# Mech_Interface_Port.net
KiCad netlist of a schematic drawn in Altium Designer
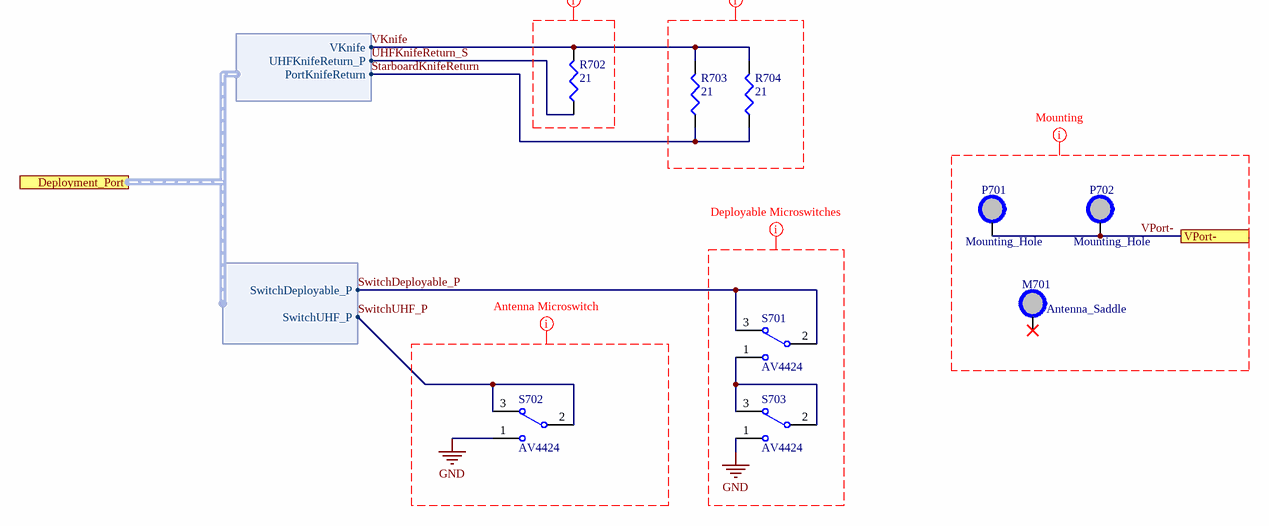
[diagram p0: Mech_Interface_Port.SchDoc]

(export (version "E")
  (design (tool "Eeschema 10.0.6"))
  (components
    (comp (ref "M701")
      (value "Antenna_Saddle")
      (footprint "ANTENNA_SADDLE")
      (fields
        (field (name "PART NUMBER") "PXX-ABS-00001")
        (field (name "MANUFACTURER PART NUMBER") "Custom")
        (field (name "PUBLISHER") "AlbertaSat")
      )
      (libsource (lib "Database") (part "Mounting_Hole"))
    )
    (comp (ref "P701")
      (value "Mounting_Hole")
      (footprint "DEPHINGE_MOUNTING_HOLE_BODY")
      (fields
        (field (name "PART NUMBER") "PXX-ABS-00004")
        (field (name "MANUFACTURER PART NUMBER") "Custom")
        (field (name "PUBLISHER") "AlbertaSat")
      )
      (libsource (lib "Database") (part "Mounting_Hole"))
    )
    (comp (ref "P702")
      (value "Mounting_Hole")
      (footprint "DEPHINGE_MOUNTING_HOLE_BODY")
      (fields
        (field (name "PART NUMBER") "PXX-ABS-00004")
        (field (name "MANUFACTURER PART NUMBER") "Custom")
        (field (name "PUBLISHER") "AlbertaSat")
      )
      (libsource (lib "Database") (part "Mounting_Hole"))
    )
    (comp (ref "R702")
      (value "21")
      (footprint "VSH-CPF1")
      (description "21 Ohms ±1% 1W Through Hole Resistor Axial Flame Proof, Moisture Resistant, Safety Metal Film")
      (fields
        (field (name "PART NUMBER") "PR-VSH-00317")
        (field (name "MANUFACTURER PART NUMBER") "CPF121R000FKEE6")
        (field (name "PUBLISHER") "AlbertaSat")
      )
      (libsource (lib "Database") (part "Res3"))
    )
    (comp (ref "R703")
      (value "21")
      (footprint "VSH-CPF1")
      (description "21 Ohms ±1% 1W Through Hole Resistor Axial Flame Proof, Moisture Resistant, Safety Metal Film")
      (fields
        (field (name "PART NUMBER") "PR-VSH-00317")
        (field (name "MANUFACTURER PART NUMBER") "CPF121R000FKEE6")
        (field (name "PUBLISHER") "AlbertaSat")
      )
      (libsource (lib "Database") (part "Res3"))
    )
    (comp (ref "R704")
      (value "21")
      (footprint "VSH-CPF1")
      (description "21 Ohms ±1% 1W Through Hole Resistor Axial Flame Proof, Moisture Resistant, Safety Metal Film")
      (fields
        (field (name "PART NUMBER") "PR-VSH-00317")
        (field (name "MANUFACTURER PART NUMBER") "CPF121R000FKEE6")
        (field (name "PUBLISHER") "AlbertaSat")
      )
      (libsource (lib "Database") (part "Res3"))
    )
    (comp (ref "S701")
      (value "AV4424")
      (footprint "PANA-AV4424")
      (description "SWITCH SNAP ACT SPDT 500MA 30V")
      (fields (field (name "PART NUMBER") "20035"))
      (libsource (lib "Database") (part "SW-SPDT"))
    )
    (comp (ref "S702")
      (value "AV4424")
      (footprint "PANA-AV4424")
      (description "SWITCH SNAP ACT SPDT 500MA 30V")
      (fields (field (name "PART NUMBER") "20035"))
      (libsource (lib "Database") (part "SW-SPDT"))
    )
    (comp (ref "S703")
      (value "AV4424")
      (footprint "PANA-AV4424")
      (description "SWITCH SNAP ACT SPDT 500MA 30V")
      (fields (field (name "PART NUMBER") "20035"))
      (libsource (lib "Database") (part "SW-SPDT"))
    )
  )
  (nets
    (net (code "2") (name "/StarboardKnifeReturn") (class "Default")
      (node (ref "R703") (pin "1") (pinfunction "1_1") (pintype "passive"))
      (node (ref "R704") (pin "1") (pinfunction "1_1") (pintype "passive"))
    )
    (net (code "3") (name "/SwitchDeployable_P") (class "Default")
      (node (ref "S701") (pin "2") (pinfunction "COM_2") (pintype "passive"))
      (node (ref "S701") (pin "3") (pinfunction "NC_3") (pintype "passive"))
    )
    (net (code "4") (name "/SwitchUHF_P") (class "Default")
      (node (ref "S702") (pin "2") (pinfunction "COM_2") (pintype "passive"))
      (node (ref "S702") (pin "3") (pinfunction "NC_3") (pintype "passive"))
    )
    (net (code "5") (name "/UHFKnifeReturn_S") (class "Default")
      (node (ref "R702") (pin "1") (pinfunction "1_1") (pintype "passive"))
    )
    (net (code "6") (name "/VKnife") (class "Default")
      (node (ref "R702") (pin "2") (pinfunction "2_2") (pintype "passive"))
      (node (ref "R703") (pin "2") (pinfunction "2_2") (pintype "passive"))
      (node (ref "R704") (pin "2") (pinfunction "2_2") (pintype "passive"))
    )
    (net (code "7") (name "/VPort-") (class "Default")
      (node (ref "P701") (pin "1") (pinfunction "0_1") (pintype "passive"))
      (node (ref "P702") (pin "1") (pinfunction "0_1") (pintype "passive"))
    )
    (net (code "9") (name "GND") (class "Default")
      (node (ref "S702") (pin "1") (pinfunction "NO_1") (pintype "passive"))
      (node (ref "S703") (pin "1") (pinfunction "NO_1") (pintype "passive"))
    )
    (net (code "10") (name "Net-(S701-NO)") (class "Default")
      (node (ref "S701") (pin "1") (pinfunction "NO_1") (pintype "passive"))
      (node (ref "S703") (pin "2") (pinfunction "COM_2") (pintype "passive"))
      (node (ref "S703") (pin "3") (pinfunction "NC_3") (pintype "passive"))
    )
    (net (code "11") (name "unconnected-(M701-0-Pad1)") (class "Default")
      (node (ref "M701") (pin "1") (pinfunction "0_1") (pintype "passive+no_connect"))
    )
  )
)
